# Device_Measurement_v1_4.net
KiCad netlist of a schematic drawn in EAGLE
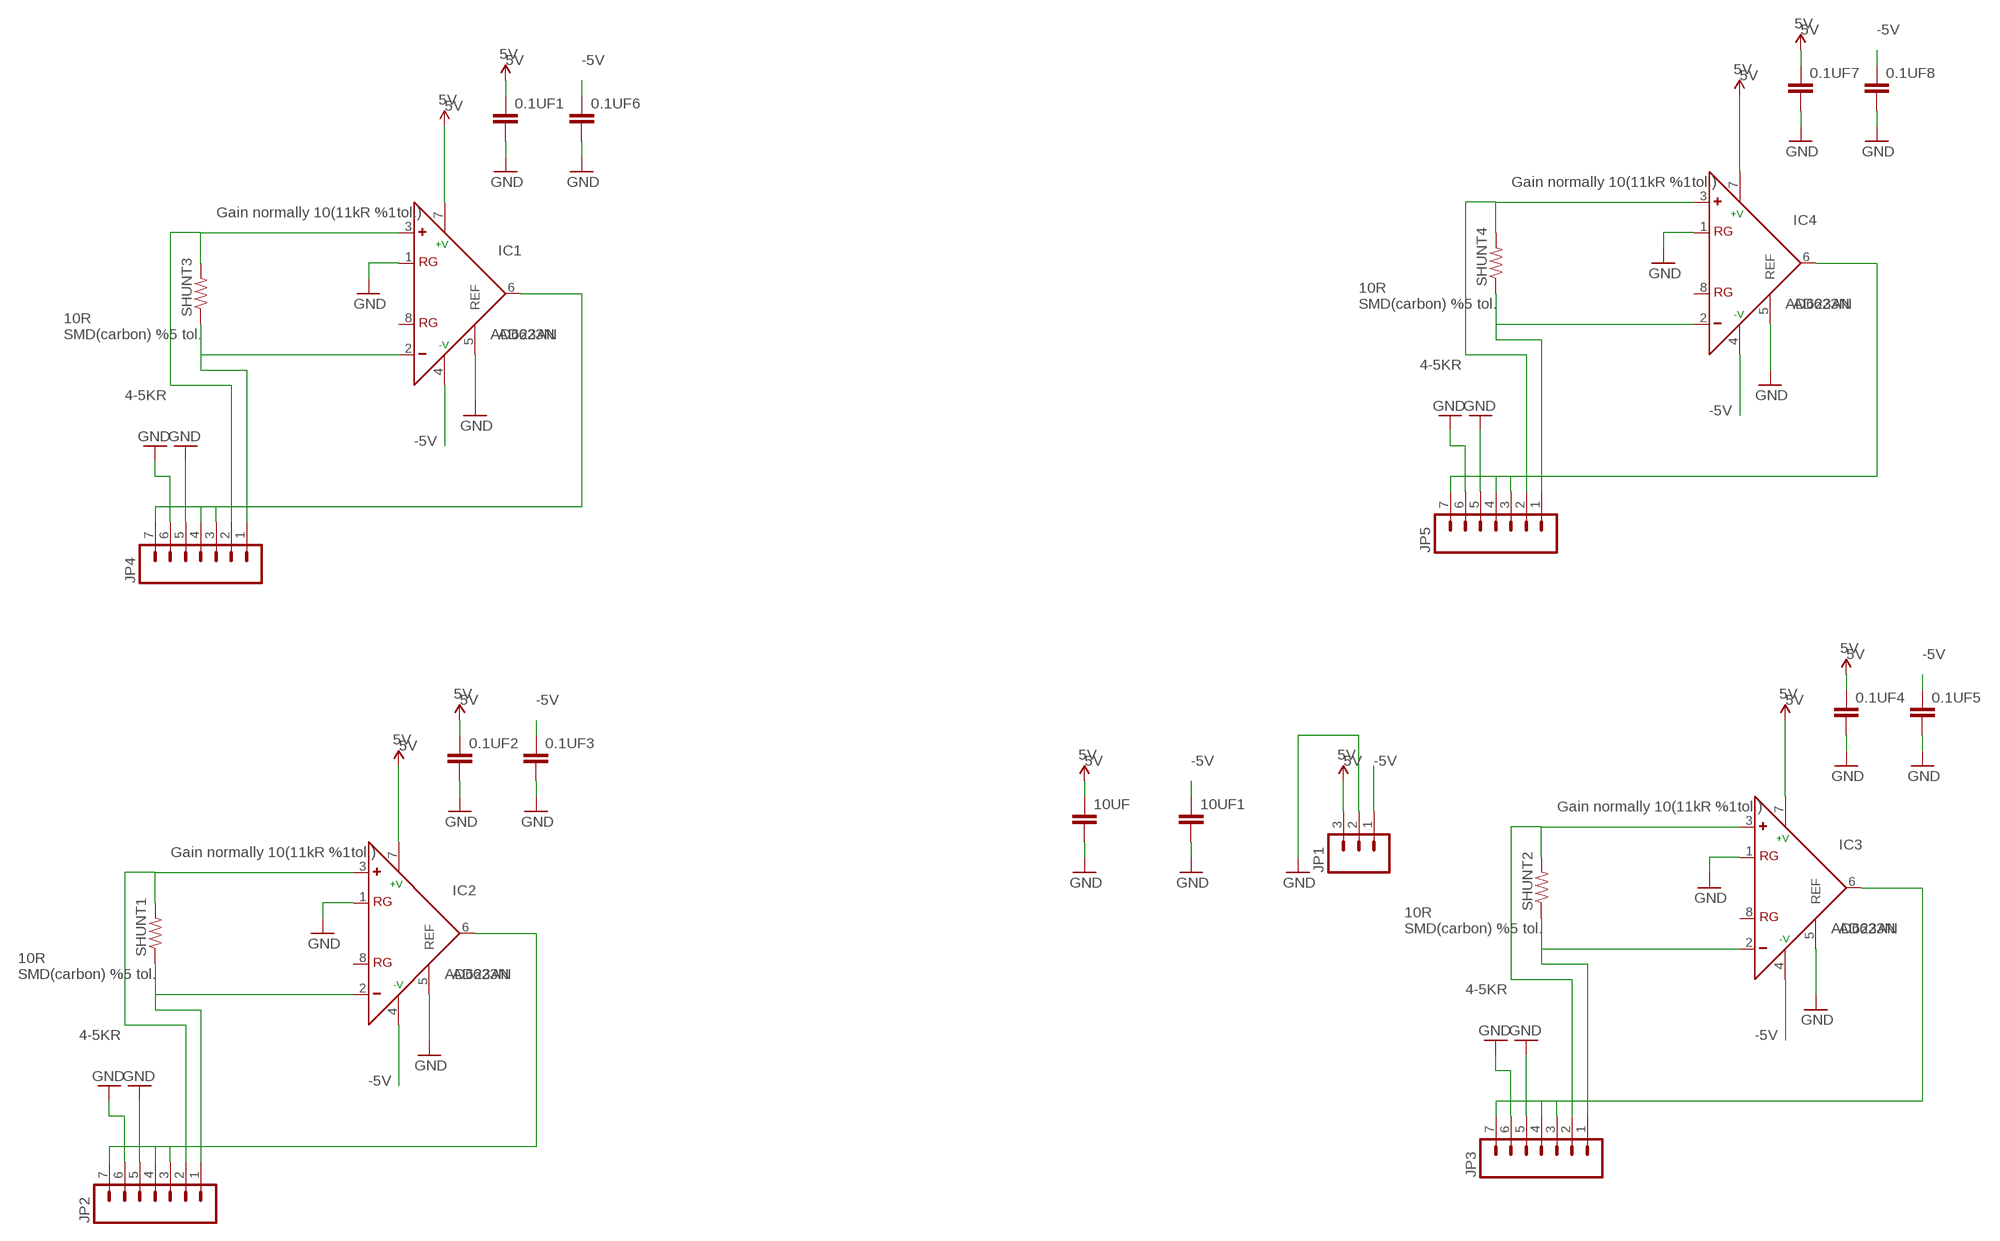
[diagram p0: schematic, sheet 1]

(export (version "E")
  (design (tool "Eeschema 10.0.6"))
  (components
    (comp (ref "0.1UF1")
      (value "CAPPTH1")
      (footprint "eagle-import:CAP-PTH-5MM")
      (libsource (lib "eagle-import") (part "CAPPTH1"))
    )
    (comp (ref "0.1UF2")
      (value "CAPPTH1")
      (footprint "eagle-import:CAP-PTH-5MM")
      (libsource (lib "eagle-import") (part "CAPPTH1"))
    )
    (comp (ref "0.1UF3")
      (value "CAPPTH1")
      (footprint "eagle-import:CAP-PTH-5MM")
      (libsource (lib "eagle-import") (part "CAPPTH1"))
    )
    (comp (ref "0.1UF4")
      (value "CAPPTH1")
      (footprint "eagle-import:CAP-PTH-5MM")
      (libsource (lib "eagle-import") (part "CAPPTH1"))
    )
    (comp (ref "0.1UF5")
      (value "CAPPTH1")
      (footprint "eagle-import:CAP-PTH-5MM")
      (libsource (lib "eagle-import") (part "CAPPTH1"))
    )
    (comp (ref "0.1UF6")
      (value "CAPPTH1")
      (footprint "eagle-import:CAP-PTH-5MM")
      (libsource (lib "eagle-import") (part "CAPPTH1"))
    )
    (comp (ref "0.1UF7")
      (value "CAPPTH1")
      (footprint "eagle-import:CAP-PTH-5MM")
      (libsource (lib "eagle-import") (part "CAPPTH1"))
    )
    (comp (ref "0.1UF8")
      (value "CAPPTH1")
      (footprint "eagle-import:CAP-PTH-5MM")
      (libsource (lib "eagle-import") (part "CAPPTH1"))
    )
    (comp (ref "10UF")
      (value "CAPPTH1")
      (footprint "eagle-import:CAP-PTH-5MM")
      (libsource (lib "eagle-import") (part "CAPPTH1"))
    )
    (comp (ref "10UF1")
      (value "CAPPTH1")
      (footprint "eagle-import:CAP-PTH-5MM")
      (libsource (lib "eagle-import") (part "CAPPTH1"))
    )
    (comp (ref "IC1")
      (value "AD623N")
      (footprint "eagle-import:DIL08")
      (fields (field (name "MF") "ALTERA CORPORATION") (field (name "MPN") "AD623ANZ"))
      (libsource (lib "eagle-import") (part "AD623N"))
    )
    (comp (ref "IC2")
      (value "AD623N")
      (footprint "eagle-import:DIL08")
      (fields (field (name "MF") "ALTERA CORPORATION") (field (name "MPN") "AD623ANZ"))
      (libsource (lib "eagle-import") (part "AD623N"))
    )
    (comp (ref "IC3")
      (value "AD623N")
      (footprint "eagle-import:DIL08")
      (fields (field (name "MF") "ALTERA CORPORATION") (field (name "MPN") "AD623ANZ"))
      (libsource (lib "eagle-import") (part "AD623N"))
    )
    (comp (ref "IC4")
      (value "AD623N")
      (footprint "eagle-import:DIL08")
      (fields (field (name "MF") "ALTERA CORPORATION") (field (name "MPN") "AD623ANZ"))
      (libsource (lib "eagle-import") (part "AD623N"))
    )
    (comp (ref "JP1")
      (value "M03LOCK")
      (footprint "eagle-import:1X03_LOCK")
      (libsource (lib "eagle-import") (part "M03LOCK"))
    )
    (comp (ref "JP2")
      (value "M07")
      (footprint "eagle-import:1X07")
      (libsource (lib "eagle-import") (part "M07"))
    )
    (comp (ref "JP3")
      (value "M07")
      (footprint "eagle-import:1X07")
      (libsource (lib "eagle-import") (part "M07"))
    )
    (comp (ref "JP4")
      (value "M07")
      (footprint "eagle-import:1X07")
      (libsource (lib "eagle-import") (part "M07"))
    )
    (comp (ref "JP5")
      (value "M07")
      (footprint "eagle-import:1X07")
      (libsource (lib "eagle-import") (part "M07"))
    )
    (comp (ref "SHUNT1")
      (value "RESISTOR1206")
      (footprint "eagle-import:1206")
      (libsource (lib "eagle-import") (part "RESISTOR1206"))
    )
    (comp (ref "SHUNT2")
      (value "RESISTOR1206")
      (footprint "eagle-import:1206")
      (libsource (lib "eagle-import") (part "RESISTOR1206"))
    )
    (comp (ref "SHUNT3")
      (value "RESISTOR1206")
      (footprint "eagle-import:1206")
      (libsource (lib "eagle-import") (part "RESISTOR1206"))
    )
    (comp (ref "SHUNT4")
      (value "RESISTOR1206")
      (footprint "eagle-import:1206")
      (libsource (lib "eagle-import") (part "RESISTOR1206"))
    )
  )
  (nets
    (net (code "1") (name "/-5V") (class "Default")
      (node (ref "0.1UF3") (pin "1") (pinfunction "1_1") (pintype "passive"))
      (node (ref "0.1UF5") (pin "1") (pinfunction "1_1") (pintype "passive"))
      (node (ref "0.1UF6") (pin "1") (pinfunction "1_1") (pintype "passive"))
      (node (ref "0.1UF8") (pin "1") (pinfunction "1_1") (pintype "passive"))
      (node (ref "10UF1") (pin "1") (pinfunction "1_1") (pintype "passive"))
      (node (ref "IC1") (pin "4") (pinfunction "-V_4") (pintype "power_in"))
      (node (ref "IC2") (pin "4") (pinfunction "-V_4") (pintype "power_in"))
      (node (ref "IC3") (pin "4") (pinfunction "-V_4") (pintype "power_in"))
      (node (ref "IC4") (pin "4") (pinfunction "-V_4") (pintype "power_in"))
      (node (ref "JP1") (pin "1") (pinfunction "1_1") (pintype "passive"))
    )
    (net (code "2") (name "5V") (class "Default")
      (node (ref "0.1UF1") (pin "1") (pinfunction "1_1") (pintype "passive"))
      (node (ref "0.1UF2") (pin "1") (pinfunction "1_1") (pintype "passive"))
      (node (ref "0.1UF4") (pin "1") (pinfunction "1_1") (pintype "passive"))
      (node (ref "0.1UF7") (pin "1") (pinfunction "1_1") (pintype "passive"))
      (node (ref "10UF") (pin "1") (pinfunction "1_1") (pintype "passive"))
      (node (ref "IC1") (pin "7") (pinfunction "+V_7") (pintype "power_in"))
      (node (ref "IC2") (pin "7") (pinfunction "+V_7") (pintype "power_in"))
      (node (ref "IC3") (pin "7") (pinfunction "+V_7") (pintype "power_in"))
      (node (ref "IC4") (pin "7") (pinfunction "+V_7") (pintype "power_in"))
      (node (ref "JP1") (pin "3") (pinfunction "3_3") (pintype "passive"))
    )
    (net (code "3") (name "GND") (class "Default")
      (node (ref "0.1UF1") (pin "2") (pinfunction "2_2") (pintype "passive"))
      (node (ref "0.1UF2") (pin "2") (pinfunction "2_2") (pintype "passive"))
      (node (ref "0.1UF3") (pin "2") (pinfunction "2_2") (pintype "passive"))
      (node (ref "0.1UF4") (pin "2") (pinfunction "2_2") (pintype "passive"))
      (node (ref "0.1UF5") (pin "2") (pinfunction "2_2") (pintype "passive"))
      (node (ref "0.1UF6") (pin "2") (pinfunction "2_2") (pintype "passive"))
      (node (ref "0.1UF7") (pin "2") (pinfunction "2_2") (pintype "passive"))
      (node (ref "0.1UF8") (pin "2") (pinfunction "2_2") (pintype "passive"))
      (node (ref "10UF") (pin "2") (pinfunction "2_2") (pintype "passive"))
      (node (ref "10UF1") (pin "2") (pinfunction "2_2") (pintype "passive"))
      (node (ref "IC1") (pin "1") (pinfunction "RG_1") (pintype "passive"))
      (node (ref "IC1") (pin "5") (pinfunction "REF_5") (pintype "passive"))
      (node (ref "IC2") (pin "1") (pinfunction "RG_1") (pintype "passive"))
      (node (ref "IC2") (pin "5") (pinfunction "REF_5") (pintype "passive"))
      (node (ref "IC3") (pin "1") (pinfunction "RG_1") (pintype "passive"))
      (node (ref "IC3") (pin "5") (pinfunction "REF_5") (pintype "passive"))
      (node (ref "IC4") (pin "1") (pinfunction "RG_1") (pintype "passive"))
      (node (ref "IC4") (pin "5") (pinfunction "REF_5") (pintype "passive"))
      (node (ref "JP1") (pin "2") (pinfunction "2_2") (pintype "passive"))
      (node (ref "JP2") (pin "5") (pinfunction "5_5") (pintype "passive"))
      (node (ref "JP2") (pin "6") (pinfunction "6_6") (pintype "passive"))
      (node (ref "JP3") (pin "5") (pinfunction "5_5") (pintype "passive"))
      (node (ref "JP3") (pin "6") (pinfunction "6_6") (pintype "passive"))
      (node (ref "JP4") (pin "5") (pinfunction "5_5") (pintype "passive"))
      (node (ref "JP4") (pin "6") (pinfunction "6_6") (pintype "passive"))
      (node (ref "JP5") (pin "5") (pinfunction "5_5") (pintype "passive"))
      (node (ref "JP5") (pin "6") (pinfunction "6_6") (pintype "passive"))
    )
    (net (code "4") (name "Net-(IC1-+)") (class "Default")
      (node (ref "IC1") (pin "3") (pinfunction "+_3") (pintype "input"))
      (node (ref "JP4") (pin "2") (pinfunction "2_2") (pintype "passive"))
      (node (ref "SHUNT3") (pin "2") (pinfunction "2_2") (pintype "passive"))
    )
    (net (code "5") (name "Net-(IC1--)") (class "Default")
      (node (ref "IC1") (pin "2") (pinfunction "-_2") (pintype "input"))
      (node (ref "JP4") (pin "1") (pinfunction "1_1") (pintype "passive"))
      (node (ref "SHUNT3") (pin "1") (pinfunction "1_1") (pintype "passive"))
    )
    (net (code "6") (name "Net-(IC1-OUT)") (class "Default")
      (node (ref "IC1") (pin "6") (pinfunction "OUT_6") (pintype "output"))
      (node (ref "JP4") (pin "7") (pinfunction "7_7") (pintype "passive"))
    )
    (net (code "7") (name "Net-(IC2-+)") (class "Default")
      (node (ref "IC2") (pin "3") (pinfunction "+_3") (pintype "input"))
      (node (ref "JP2") (pin "2") (pinfunction "2_2") (pintype "passive"))
      (node (ref "SHUNT1") (pin "2") (pinfunction "2_2") (pintype "passive"))
    )
    (net (code "8") (name "Net-(IC2--)") (class "Default")
      (node (ref "IC2") (pin "2") (pinfunction "-_2") (pintype "input"))
      (node (ref "JP2") (pin "1") (pinfunction "1_1") (pintype "passive"))
      (node (ref "SHUNT1") (pin "1") (pinfunction "1_1") (pintype "passive"))
    )
    (net (code "9") (name "Net-(IC2-OUT)") (class "Default")
      (node (ref "IC2") (pin "6") (pinfunction "OUT_6") (pintype "output"))
      (node (ref "JP2") (pin "7") (pinfunction "7_7") (pintype "passive"))
    )
    (net (code "10") (name "Net-(IC3-+)") (class "Default")
      (node (ref "IC3") (pin "3") (pinfunction "+_3") (pintype "input"))
      (node (ref "JP3") (pin "2") (pinfunction "2_2") (pintype "passive"))
      (node (ref "SHUNT2") (pin "2") (pinfunction "2_2") (pintype "passive"))
    )
    (net (code "11") (name "Net-(IC3--)") (class "Default")
      (node (ref "IC3") (pin "2") (pinfunction "-_2") (pintype "input"))
      (node (ref "JP3") (pin "1") (pinfunction "1_1") (pintype "passive"))
      (node (ref "SHUNT2") (pin "1") (pinfunction "1_1") (pintype "passive"))
    )
    (net (code "12") (name "Net-(IC3-OUT)") (class "Default")
      (node (ref "IC3") (pin "6") (pinfunction "OUT_6") (pintype "output"))
      (node (ref "JP3") (pin "7") (pinfunction "7_7") (pintype "passive"))
    )
    (net (code "13") (name "Net-(IC4-+)") (class "Default")
      (node (ref "IC4") (pin "3") (pinfunction "+_3") (pintype "input"))
      (node (ref "JP5") (pin "2") (pinfunction "2_2") (pintype "passive"))
      (node (ref "SHUNT4") (pin "2") (pinfunction "2_2") (pintype "passive"))
    )
    (net (code "14") (name "Net-(IC4--)") (class "Default")
      (node (ref "IC4") (pin "2") (pinfunction "-_2") (pintype "input"))
      (node (ref "JP5") (pin "1") (pinfunction "1_1") (pintype "passive"))
      (node (ref "SHUNT4") (pin "1") (pinfunction "1_1") (pintype "passive"))
    )
    (net (code "15") (name "Net-(IC4-OUT)") (class "Default")
      (node (ref "IC4") (pin "6") (pinfunction "OUT_6") (pintype "output"))
      (node (ref "JP5") (pin "7") (pinfunction "7_7") (pintype "passive"))
    )
    (net (code "16") (name "Net-(JP2-Pad3)") (class "Default")
      (node (ref "JP2") (pin "3") (pinfunction "3_3") (pintype "passive"))
      (node (ref "JP2") (pin "4") (pinfunction "4_4") (pintype "passive"))
    )
    (net (code "17") (name "Net-(JP3-Pad3)") (class "Default")
      (node (ref "JP3") (pin "3") (pinfunction "3_3") (pintype "passive"))
      (node (ref "JP3") (pin "4") (pinfunction "4_4") (pintype "passive"))
    )
    (net (code "18") (name "Net-(JP4-Pad3)") (class "Default")
      (node (ref "JP4") (pin "3") (pinfunction "3_3") (pintype "passive"))
      (node (ref "JP4") (pin "4") (pinfunction "4_4") (pintype "passive"))
    )
    (net (code "19") (name "Net-(JP5-Pad3)") (class "Default")
      (node (ref "JP5") (pin "3") (pinfunction "3_3") (pintype "passive"))
      (node (ref "JP5") (pin "4") (pinfunction "4_4") (pintype "passive"))
    )
    (net (code "20") (name "unconnected-(IC1-RG-Pad8)") (class "Default")
      (node (ref "IC1") (pin "8") (pinfunction "RG_8") (pintype "passive"))
    )
    (net (code "21") (name "unconnected-(IC2-RG-Pad8)") (class "Default")
      (node (ref "IC2") (pin "8") (pinfunction "RG_8") (pintype "passive"))
    )
    (net (code "22") (name "unconnected-(IC3-RG-Pad8)") (class "Default")
      (node (ref "IC3") (pin "8") (pinfunction "RG_8") (pintype "passive"))
    )
    (net (code "23") (name "unconnected-(IC4-RG-Pad8)") (class "Default")
      (node (ref "IC4") (pin "8") (pinfunction "RG_8") (pintype "passive"))
    )
  )
)
